# EM_Harp.net
KiCad netlist of a schematic drawn in EAGLE
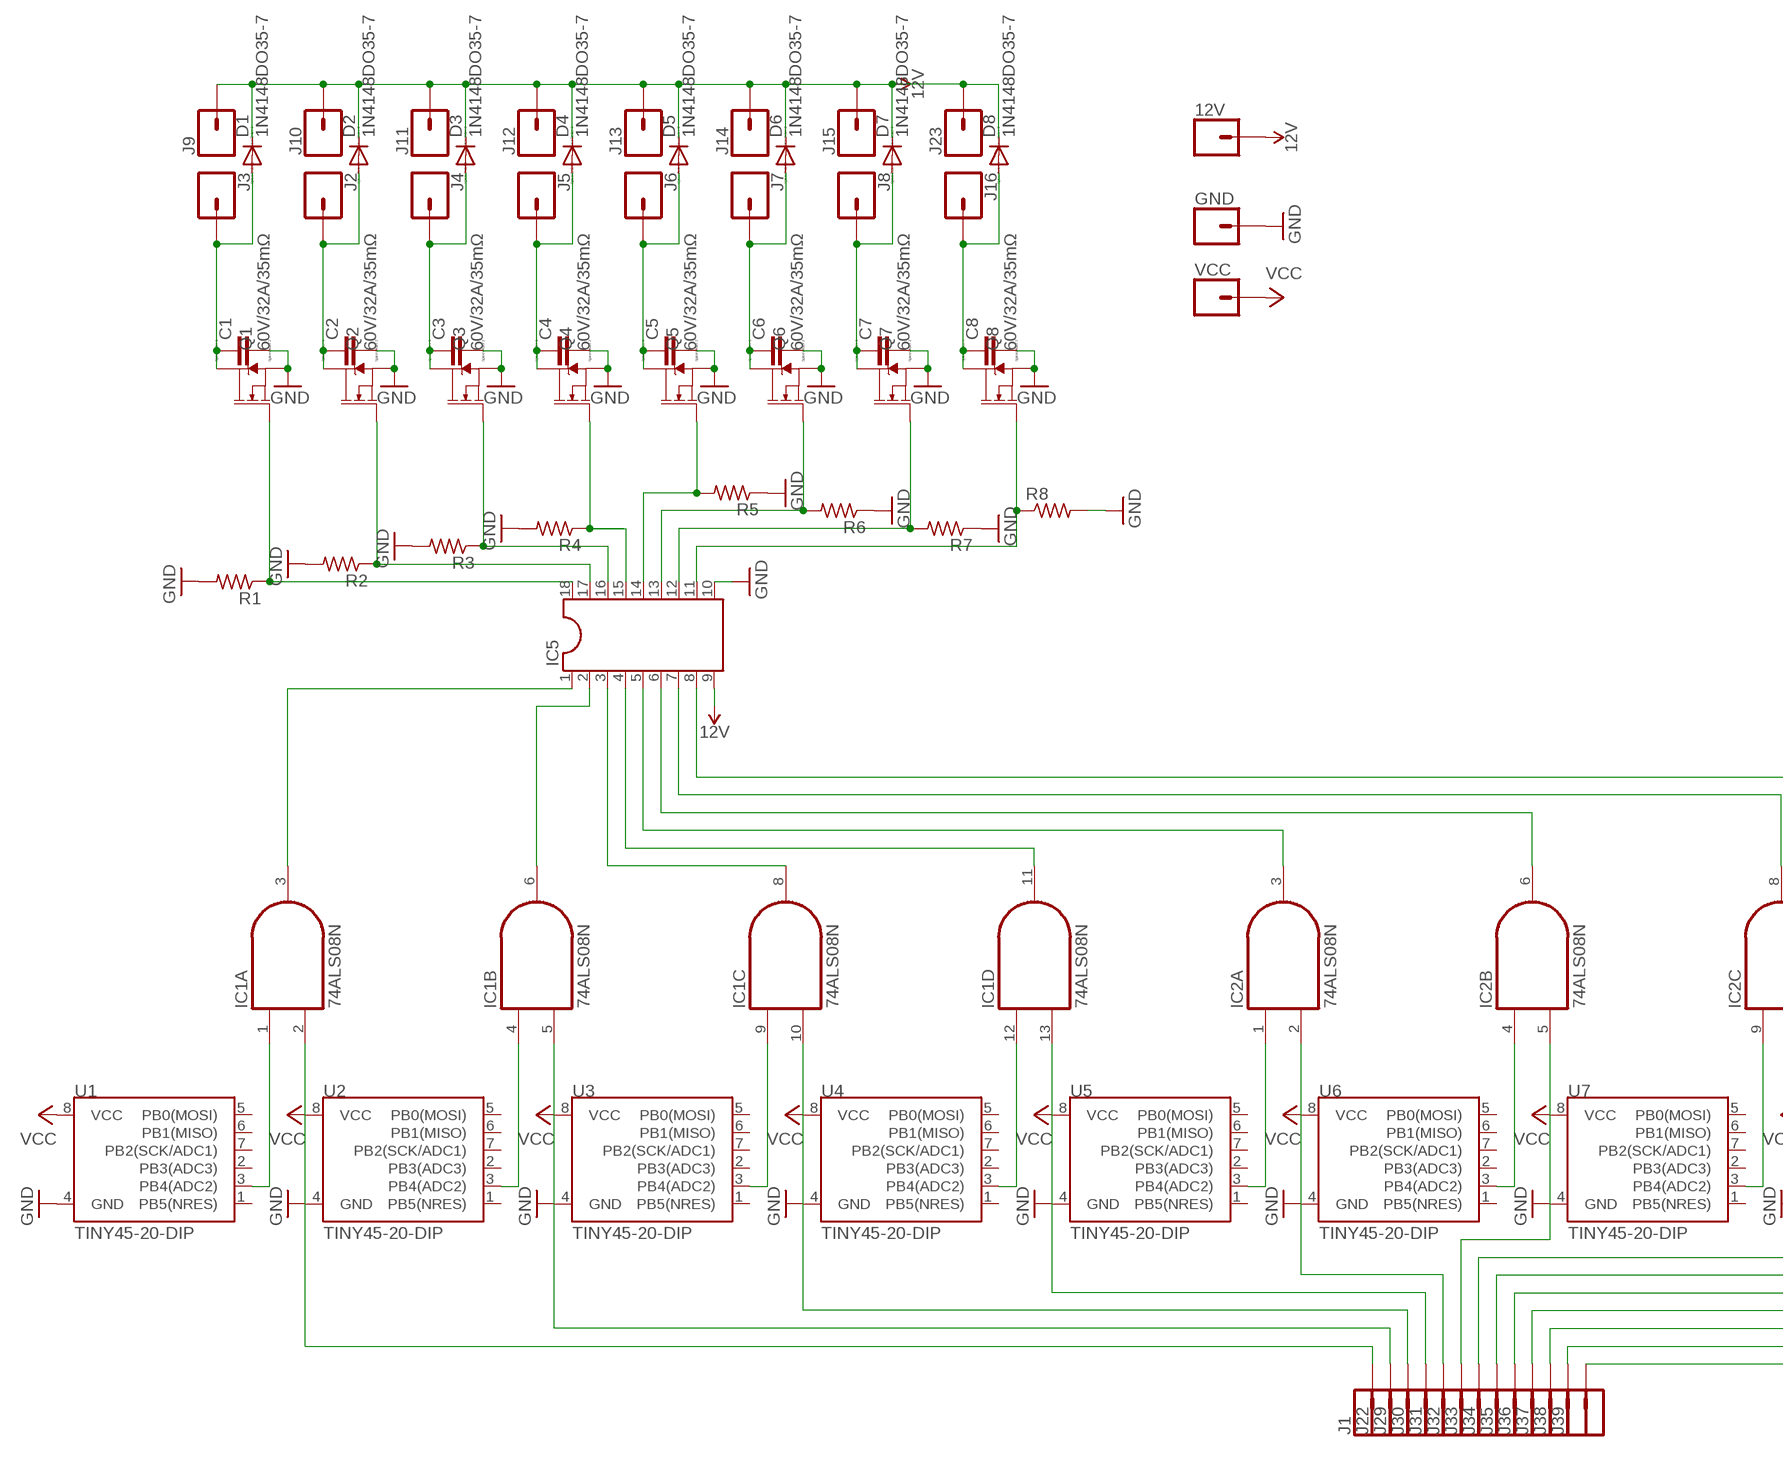
[diagram p0: schematic, sheet 1, part 1 of 2]
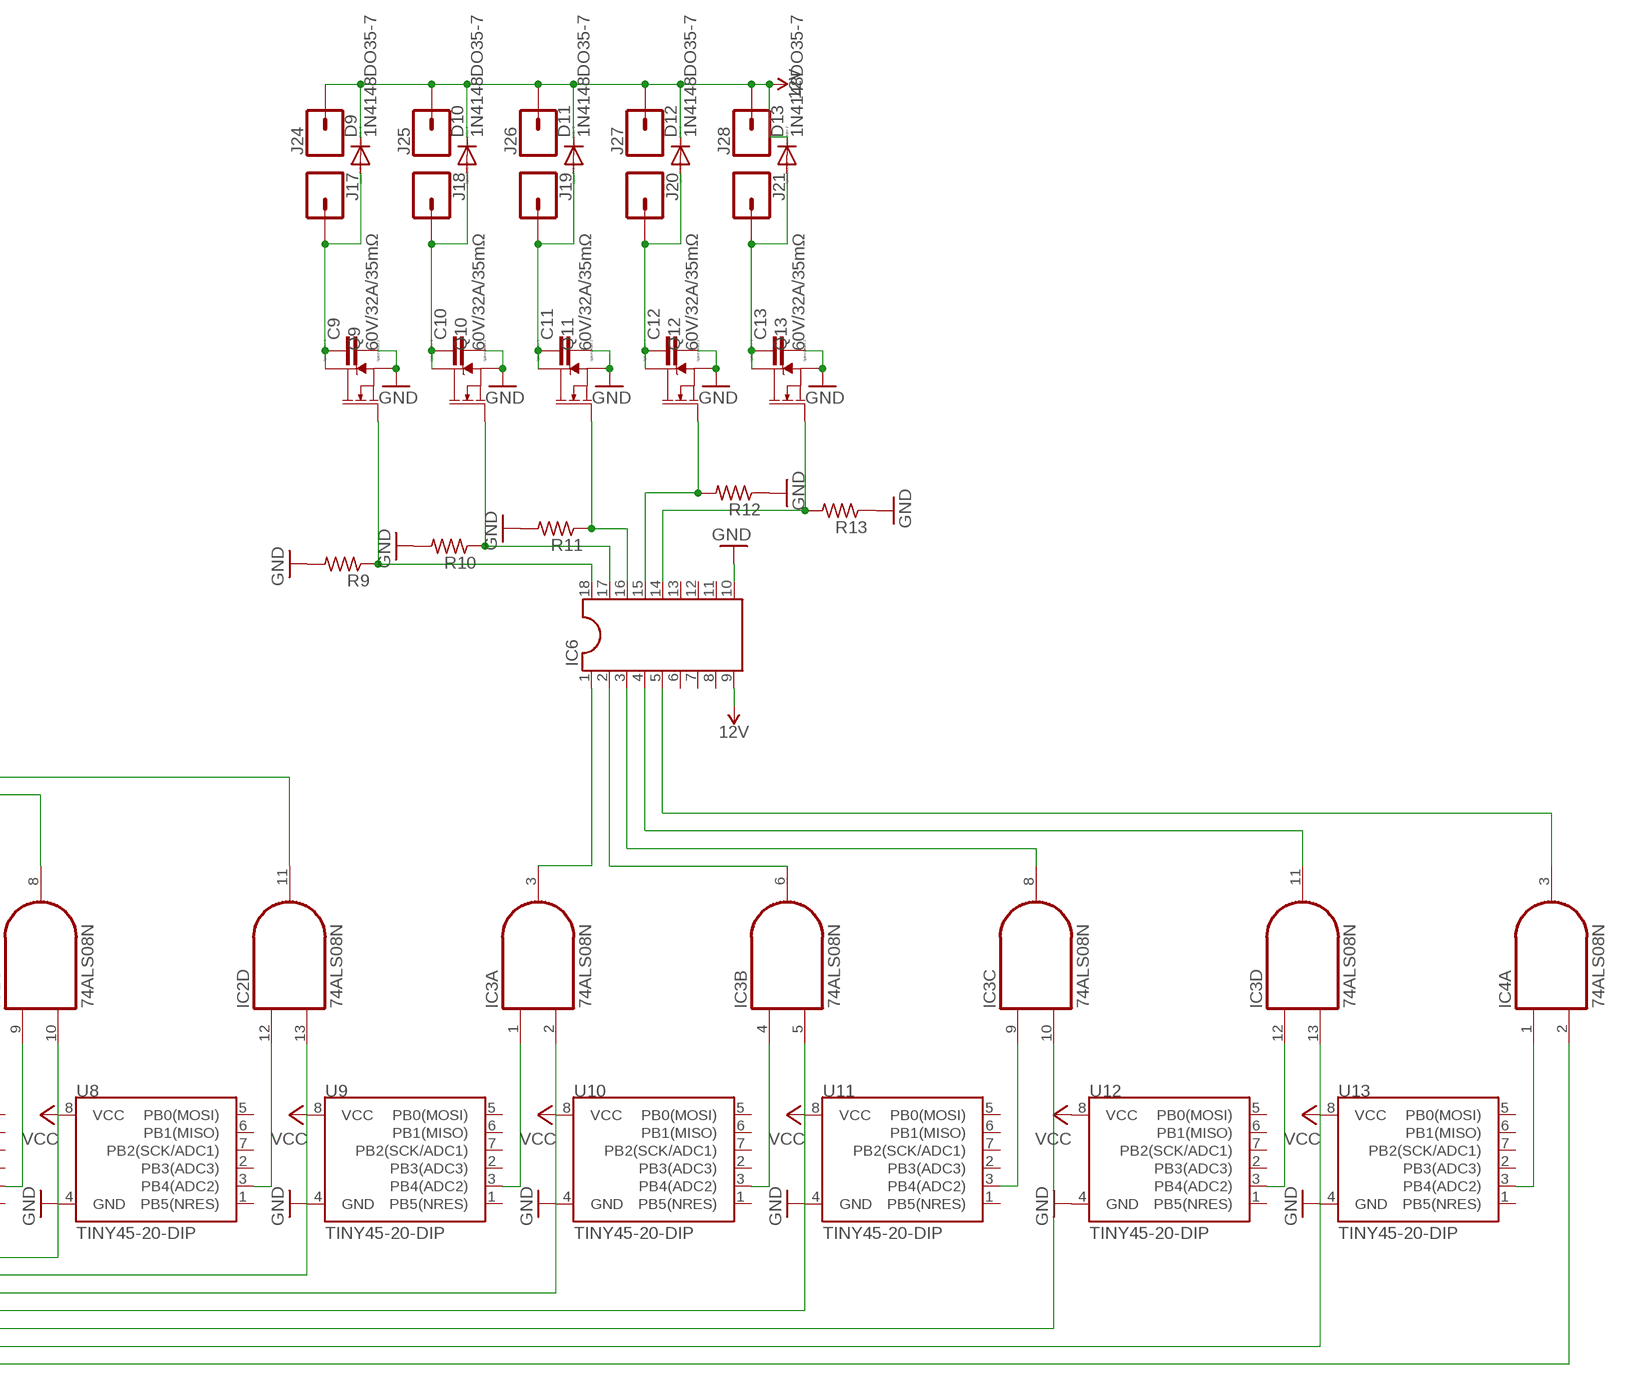
[diagram p1: schematic, sheet 1, part 2 of 2]

(export (version "E")
  (design (tool "Eeschema 10.0.6"))
  (components
    (comp (ref "12V")
      (value "CONN_01")
      (footprint "eagle-import:1X01")
      (libsource (lib "eagle-import") (part "CONN_01"))
    )
    (comp (ref "C1") (value "C") (footprint "eagle-import:C0805") (libsource (lib "eagle-import") (part "C")))
    (comp (ref "C2") (value "C") (footprint "eagle-import:C0805") (libsource (lib "eagle-import") (part "C")))
    (comp (ref "C3") (value "C") (footprint "eagle-import:C0805") (libsource (lib "eagle-import") (part "C")))
    (comp (ref "C4") (value "C") (footprint "eagle-import:C0805") (libsource (lib "eagle-import") (part "C")))
    (comp (ref "C5") (value "C") (footprint "eagle-import:C0805") (libsource (lib "eagle-import") (part "C")))
    (comp (ref "C6") (value "C") (footprint "eagle-import:C0805") (libsource (lib "eagle-import") (part "C")))
    (comp (ref "C7") (value "C") (footprint "eagle-import:C0805") (libsource (lib "eagle-import") (part "C")))
    (comp (ref "C8") (value "C") (footprint "eagle-import:C0805") (libsource (lib "eagle-import") (part "C")))
    (comp (ref "C9") (value "C") (footprint "eagle-import:C0805") (libsource (lib "eagle-import") (part "C")))
    (comp (ref "C10")
      (value "C")
      (footprint "eagle-import:C0805")
      (libsource (lib "eagle-import") (part "C"))
    )
    (comp (ref "C11")
      (value "C")
      (footprint "eagle-import:C0805")
      (libsource (lib "eagle-import") (part "C"))
    )
    (comp (ref "C12")
      (value "C")
      (footprint "eagle-import:C0805")
      (libsource (lib "eagle-import") (part "C"))
    )
    (comp (ref "C13")
      (value "C")
      (footprint "eagle-import:C0805")
      (libsource (lib "eagle-import") (part "C"))
    )
    (comp (ref "D1")
      (value "1N4148DO35-7")
      (footprint "eagle-import:DO35-7")
      (libsource (lib "eagle-import") (part "1N4148DO35-7"))
    )
    (comp (ref "D2")
      (value "1N4148DO35-7")
      (footprint "eagle-import:DO35-7")
      (libsource (lib "eagle-import") (part "1N4148DO35-7"))
    )
    (comp (ref "D3")
      (value "1N4148DO35-7")
      (footprint "eagle-import:DO35-7")
      (libsource (lib "eagle-import") (part "1N4148DO35-7"))
    )
    (comp (ref "D4")
      (value "1N4148DO35-7")
      (footprint "eagle-import:DO35-7")
      (libsource (lib "eagle-import") (part "1N4148DO35-7"))
    )
    (comp (ref "D5")
      (value "1N4148DO35-7")
      (footprint "eagle-import:DO35-7")
      (libsource (lib "eagle-import") (part "1N4148DO35-7"))
    )
    (comp (ref "D6")
      (value "1N4148DO35-7")
      (footprint "eagle-import:DO35-7")
      (libsource (lib "eagle-import") (part "1N4148DO35-7"))
    )
    (comp (ref "D7")
      (value "1N4148DO35-7")
      (footprint "eagle-import:DO35-7")
      (libsource (lib "eagle-import") (part "1N4148DO35-7"))
    )
    (comp (ref "D8")
      (value "1N4148DO35-7")
      (footprint "eagle-import:DO35-7")
      (libsource (lib "eagle-import") (part "1N4148DO35-7"))
    )
    (comp (ref "D9")
      (value "1N4148DO35-7")
      (footprint "eagle-import:DO35-7")
      (libsource (lib "eagle-import") (part "1N4148DO35-7"))
    )
    (comp (ref "D10")
      (value "1N4148DO35-7")
      (footprint "eagle-import:DO35-7")
      (libsource (lib "eagle-import") (part "1N4148DO35-7"))
    )
    (comp (ref "D11")
      (value "1N4148DO35-7")
      (footprint "eagle-import:DO35-7")
      (libsource (lib "eagle-import") (part "1N4148DO35-7"))
    )
    (comp (ref "D12")
      (value "1N4148DO35-7")
      (footprint "eagle-import:DO35-7")
      (libsource (lib "eagle-import") (part "1N4148DO35-7"))
    )
    (comp (ref "D13")
      (value "1N4148DO35-7")
      (footprint "eagle-import:DO35-7")
      (libsource (lib "eagle-import") (part "1N4148DO35-7"))
    )
    (comp (ref "GND")
      (value "CONN_01")
      (footprint "eagle-import:1X01")
      (libsource (lib "eagle-import") (part "CONN_01"))
    )
    (comp (ref "IC1")
      (value "74ALS08N")
      (footprint "eagle-import:DIL14")
      (libsource (lib "eagle-import") (part "7408NALS"))
    )
    (comp (ref "IC2")
      (value "74ALS08N")
      (footprint "eagle-import:DIL14")
      (libsource (lib "eagle-import") (part "7408NALS"))
    )
    (comp (ref "IC3")
      (value "74ALS08N")
      (footprint "eagle-import:DIL14")
      (libsource (lib "eagle-import") (part "7408NALS"))
    )
    (comp (ref "IC4")
      (value "74ALS08N")
      (footprint "eagle-import:DIL14")
      (libsource (lib "eagle-import") (part "7408NALS"))
    )
    (comp (ref "IC5")
      (value "DIL18")
      (footprint "eagle-import:DIL18")
      (libsource (lib "eagle-import") (part "DIL18"))
    )
    (comp (ref "IC6")
      (value "DIL18")
      (footprint "eagle-import:DIL18")
      (libsource (lib "eagle-import") (part "DIL18"))
    )
    (comp (ref "J1")
      (value "CONN_01")
      (footprint "eagle-import:1X01")
      (libsource (lib "eagle-import") (part "CONN_01"))
    )
    (comp (ref "J2")
      (value "CONN_01")
      (footprint "eagle-import:1X01")
      (libsource (lib "eagle-import") (part "CONN_01"))
    )
    (comp (ref "J3")
      (value "CONN_01")
      (footprint "eagle-import:1X01")
      (libsource (lib "eagle-import") (part "CONN_01"))
    )
    (comp (ref "J4")
      (value "CONN_01")
      (footprint "eagle-import:1X01")
      (libsource (lib "eagle-import") (part "CONN_01"))
    )
    (comp (ref "J5")
      (value "CONN_01")
      (footprint "eagle-import:1X01")
      (libsource (lib "eagle-import") (part "CONN_01"))
    )
    (comp (ref "J6")
      (value "CONN_01")
      (footprint "eagle-import:1X01")
      (libsource (lib "eagle-import") (part "CONN_01"))
    )
    (comp (ref "J7")
      (value "CONN_01")
      (footprint "eagle-import:1X01")
      (libsource (lib "eagle-import") (part "CONN_01"))
    )
    (comp (ref "J8")
      (value "CONN_01")
      (footprint "eagle-import:1X01")
      (libsource (lib "eagle-import") (part "CONN_01"))
    )
    (comp (ref "J9")
      (value "CONN_01")
      (footprint "eagle-import:1X01")
      (libsource (lib "eagle-import") (part "CONN_01"))
    )
    (comp (ref "J10")
      (value "CONN_01")
      (footprint "eagle-import:1X01")
      (libsource (lib "eagle-import") (part "CONN_01"))
    )
    (comp (ref "J11")
      (value "CONN_01")
      (footprint "eagle-import:1X01")
      (libsource (lib "eagle-import") (part "CONN_01"))
    )
    (comp (ref "J12")
      (value "CONN_01")
      (footprint "eagle-import:1X01")
      (libsource (lib "eagle-import") (part "CONN_01"))
    )
    (comp (ref "J13")
      (value "CONN_01")
      (footprint "eagle-import:1X01")
      (libsource (lib "eagle-import") (part "CONN_01"))
    )
    (comp (ref "J14")
      (value "CONN_01")
      (footprint "eagle-import:1X01")
      (libsource (lib "eagle-import") (part "CONN_01"))
    )
    (comp (ref "J15")
      (value "CONN_01")
      (footprint "eagle-import:1X01")
      (libsource (lib "eagle-import") (part "CONN_01"))
    )
    (comp (ref "J16")
      (value "CONN_01")
      (footprint "eagle-import:1X01")
      (libsource (lib "eagle-import") (part "CONN_01"))
    )
    (comp (ref "J17")
      (value "CONN_01")
      (footprint "eagle-import:1X01")
      (libsource (lib "eagle-import") (part "CONN_01"))
    )
    (comp (ref "J18")
      (value "CONN_01")
      (footprint "eagle-import:1X01")
      (libsource (lib "eagle-import") (part "CONN_01"))
    )
    (comp (ref "J19")
      (value "CONN_01")
      (footprint "eagle-import:1X01")
      (libsource (lib "eagle-import") (part "CONN_01"))
    )
    (comp (ref "J20")
      (value "CONN_01")
      (footprint "eagle-import:1X01")
      (libsource (lib "eagle-import") (part "CONN_01"))
    )
    (comp (ref "J21")
      (value "CONN_01")
      (footprint "eagle-import:1X01")
      (libsource (lib "eagle-import") (part "CONN_01"))
    )
    (comp (ref "J22")
      (value "CONN_01")
      (footprint "eagle-import:1X01")
      (libsource (lib "eagle-import") (part "CONN_01"))
    )
    (comp (ref "J23")
      (value "CONN_01")
      (footprint "eagle-import:1X01")
      (libsource (lib "eagle-import") (part "CONN_01"))
    )
    (comp (ref "J24")
      (value "CONN_01")
      (footprint "eagle-import:1X01")
      (libsource (lib "eagle-import") (part "CONN_01"))
    )
    (comp (ref "J25")
      (value "CONN_01")
      (footprint "eagle-import:1X01")
      (libsource (lib "eagle-import") (part "CONN_01"))
    )
    (comp (ref "J26")
      (value "CONN_01")
      (footprint "eagle-import:1X01")
      (libsource (lib "eagle-import") (part "CONN_01"))
    )
    (comp (ref "J27")
      (value "CONN_01")
      (footprint "eagle-import:1X01")
      (libsource (lib "eagle-import") (part "CONN_01"))
    )
    (comp (ref "J28")
      (value "CONN_01")
      (footprint "eagle-import:1X01")
      (libsource (lib "eagle-import") (part "CONN_01"))
    )
    (comp (ref "J29")
      (value "CONN_01")
      (footprint "eagle-import:1X01")
      (libsource (lib "eagle-import") (part "CONN_01"))
    )
    (comp (ref "J30")
      (value "CONN_01")
      (footprint "eagle-import:1X01")
      (libsource (lib "eagle-import") (part "CONN_01"))
    )
    (comp (ref "J31")
      (value "CONN_01")
      (footprint "eagle-import:1X01")
      (libsource (lib "eagle-import") (part "CONN_01"))
    )
    (comp (ref "J32")
      (value "CONN_01")
      (footprint "eagle-import:1X01")
      (libsource (lib "eagle-import") (part "CONN_01"))
    )
    (comp (ref "J33")
      (value "CONN_01")
      (footprint "eagle-import:1X01")
      (libsource (lib "eagle-import") (part "CONN_01"))
    )
    (comp (ref "J34")
      (value "CONN_01")
      (footprint "eagle-import:1X01")
      (libsource (lib "eagle-import") (part "CONN_01"))
    )
    (comp (ref "J35")
      (value "CONN_01")
      (footprint "eagle-import:1X01")
      (libsource (lib "eagle-import") (part "CONN_01"))
    )
    (comp (ref "J36")
      (value "CONN_01")
      (footprint "eagle-import:1X01")
      (libsource (lib "eagle-import") (part "CONN_01"))
    )
    (comp (ref "J37")
      (value "CONN_01")
      (footprint "eagle-import:1X01")
      (libsource (lib "eagle-import") (part "CONN_01"))
    )
    (comp (ref "J38")
      (value "CONN_01")
      (footprint "eagle-import:1X01")
      (libsource (lib "eagle-import") (part "CONN_01"))
    )
    (comp (ref "J39")
      (value "CONN_01")
      (footprint "eagle-import:1X01")
      (libsource (lib "eagle-import") (part "CONN_01"))
    )
    (comp (ref "Q1")
      (value "60V/32A/35mΩ")
      (footprint "eagle-import:TO220V")
      (libsource (lib "eagle-import") (part "MOSFET-NCH-FQP30N06L"))
    )
    (comp (ref "Q2")
      (value "60V/32A/35mΩ")
      (footprint "eagle-import:TO220V")
      (libsource (lib "eagle-import") (part "MOSFET-NCH-FQP30N06L"))
    )
    (comp (ref "Q3")
      (value "60V/32A/35mΩ")
      (footprint "eagle-import:TO220V")
      (libsource (lib "eagle-import") (part "MOSFET-NCH-FQP30N06L"))
    )
    (comp (ref "Q4")
      (value "60V/32A/35mΩ")
      (footprint "eagle-import:TO220V")
      (libsource (lib "eagle-import") (part "MOSFET-NCH-FQP30N06L"))
    )
    (comp (ref "Q5")
      (value "60V/32A/35mΩ")
      (footprint "eagle-import:TO220V")
      (libsource (lib "eagle-import") (part "MOSFET-NCH-FQP30N06L"))
    )
    (comp (ref "Q6")
      (value "60V/32A/35mΩ")
      (footprint "eagle-import:TO220V")
      (libsource (lib "eagle-import") (part "MOSFET-NCH-FQP30N06L"))
    )
    (comp (ref "Q7")
      (value "60V/32A/35mΩ")
      (footprint "eagle-import:TO220V")
      (libsource (lib "eagle-import") (part "MOSFET-NCH-FQP30N06L"))
    )
    (comp (ref "Q8")
      (value "60V/32A/35mΩ")
      (footprint "eagle-import:TO220V")
      (libsource (lib "eagle-import") (part "MOSFET-NCH-FQP30N06L"))
    )
    (comp (ref "Q9")
      (value "60V/32A/35mΩ")
      (footprint "eagle-import:TO220V")
      (libsource (lib "eagle-import") (part "MOSFET-NCH-FQP30N06L"))
    )
    (comp (ref "Q10")
      (value "60V/32A/35mΩ")
      (footprint "eagle-import:TO220V")
      (libsource (lib "eagle-import") (part "MOSFET-NCH-FQP30N06L"))
    )
    (comp (ref "Q11")
      (value "60V/32A/35mΩ")
      (footprint "eagle-import:TO220V")
      (libsource (lib "eagle-import") (part "MOSFET-NCH-FQP30N06L"))
    )
    (comp (ref "Q12")
      (value "60V/32A/35mΩ")
      (footprint "eagle-import:TO220V")
      (libsource (lib "eagle-import") (part "MOSFET-NCH-FQP30N06L"))
    )
    (comp (ref "Q13")
      (value "60V/32A/35mΩ")
      (footprint "eagle-import:TO220V")
      (libsource (lib "eagle-import") (part "MOSFET-NCH-FQP30N06L"))
    )
    (comp (ref "R1")
      (value "R-US_M0805")
      (footprint "eagle-import:M0805")
      (libsource (lib "eagle-import") (part "R-US_M0805"))
    )
    (comp (ref "R2")
      (value "R-US_R0805")
      (footprint "eagle-import:R0805")
      (libsource (lib "eagle-import") (part "R-US_R0805"))
    )
    (comp (ref "R3")
      (value "R-US_R0805")
      (footprint "eagle-import:R0805")
      (libsource (lib "eagle-import") (part "R-US_R0805"))
    )
    (comp (ref "R4")
      (value "R-US_R0805")
      (footprint "eagle-import:R0805")
      (libsource (lib "eagle-import") (part "R-US_R0805"))
    )
    (comp (ref "R5")
      (value "R-US_R0805")
      (footprint "eagle-import:R0805")
      (libsource (lib "eagle-import") (part "R-US_R0805"))
    )
    (comp (ref "R6")
      (value "R-US_R0805")
      (footprint "eagle-import:R0805")
      (libsource (lib "eagle-import") (part "R-US_R0805"))
    )
    (comp (ref "R7")
      (value "R-US_R0805")
      (footprint "eagle-import:R0805")
      (libsource (lib "eagle-import") (part "R-US_R0805"))
    )
    (comp (ref "R8")
      (value "R-US_R0805")
      (footprint "eagle-import:R0805")
      (libsource (lib "eagle-import") (part "R-US_R0805"))
    )
    (comp (ref "R9")
      (value "R-US_R0805")
      (footprint "eagle-import:R0805")
      (libsource (lib "eagle-import") (part "R-US_R0805"))
    )
    (comp (ref "R10")
      (value "R-US_R0805")
      (footprint "eagle-import:R0805")
      (libsource (lib "eagle-import") (part "R-US_R0805"))
    )
    (comp (ref "R11")
      (value "R-US_R0805")
      (footprint "eagle-import:R0805")
      (libsource (lib "eagle-import") (part "R-US_R0805"))
    )
    (comp (ref "R12")
      (value "R-US_R0805")
      (footprint "eagle-import:R0805")
      (libsource (lib "eagle-import") (part "R-US_R0805"))
    )
    (comp (ref "R13")
      (value "R-US_R0805")
      (footprint "eagle-import:R0805")
      (libsource (lib "eagle-import") (part "R-US_R0805"))
    )
    (comp (ref "U1")
      (value "TINY45-20-DIP")
      (footprint "eagle-import:DIP08_MCU")
      (libsource (lib "eagle-import") (part "ATTINY45TINY45-20-DIP"))
    )
    (comp (ref "U2")
      (value "TINY45-20-DIP")
      (footprint "eagle-import:DIP08_MCU")
      (libsource (lib "eagle-import") (part "ATTINY45TINY45-20-DIP"))
    )
    (comp (ref "U3")
      (value "TINY45-20-DIP")
      (footprint "eagle-import:DIP08_MCU")
      (libsource (lib "eagle-import") (part "ATTINY45TINY45-20-DIP"))
    )
    (comp (ref "U4")
      (value "TINY45-20-DIP")
      (footprint "eagle-import:DIP08_MCU")
      (libsource (lib "eagle-import") (part "ATTINY45TINY45-20-DIP"))
    )
    (comp (ref "U5")
      (value "TINY45-20-DIP")
      (footprint "eagle-import:DIP08_MCU")
      (libsource (lib "eagle-import") (part "ATTINY45TINY45-20-DIP"))
    )
    (comp (ref "U6")
      (value "TINY45-20-DIP")
      (footprint "eagle-import:DIP08_MCU")
      (libsource (lib "eagle-import") (part "ATTINY45TINY45-20-DIP"))
    )
    (comp (ref "U7")
      (value "TINY45-20-DIP")
      (footprint "eagle-import:DIP08_MCU")
      (libsource (lib "eagle-import") (part "ATTINY45TINY45-20-DIP"))
    )
    (comp (ref "U8")
      (value "TINY45-20-DIP")
      (footprint "eagle-import:DIP08_MCU")
      (libsource (lib "eagle-import") (part "ATTINY45TINY45-20-DIP"))
    )
    (comp (ref "U9")
      (value "TINY45-20-DIP")
      (footprint "eagle-import:DIP08_MCU")
      (libsource (lib "eagle-import") (part "ATTINY45TINY45-20-DIP"))
    )
    (comp (ref "U10")
      (value "TINY45-20-DIP")
      (footprint "eagle-import:DIP08_MCU")
      (libsource (lib "eagle-import") (part "ATTINY45TINY45-20-DIP"))
    )
    (comp (ref "U11")
      (value "TINY45-20-DIP")
      (footprint "eagle-import:DIP08_MCU")
      (libsource (lib "eagle-import") (part "ATTINY45TINY45-20-DIP"))
    )
    (comp (ref "U12")
      (value "TINY45-20-DIP")
      (footprint "eagle-import:DIP08_MCU")
      (libsource (lib "eagle-import") (part "ATTINY45TINY45-20-DIP"))
    )
    (comp (ref "U13")
      (value "TINY45-20-DIP")
      (footprint "eagle-import:DIP08_MCU")
      (libsource (lib "eagle-import") (part "ATTINY45TINY45-20-DIP"))
    )
    (comp (ref "VCC")
      (value "CONN_01")
      (footprint "eagle-import:1X01")
      (libsource (lib "eagle-import") (part "CONN_01"))
    )
  )
  (nets
    (net (code "1") (name "12V") (class "Default")
      (node (ref "12V") (pin "1") (pinfunction "1_1") (pintype "passive"))
      (node (ref "D1") (pin "C") (pinfunction "C_C") (pintype "passive"))
      (node (ref "D10") (pin "C") (pinfunction "C_C") (pintype "passive"))
      (node (ref "D11") (pin "C") (pinfunction "C_C") (pintype "passive"))
      (node (ref "D12") (pin "C") (pinfunction "C_C") (pintype "passive"))
      (node (ref "D13") (pin "C") (pinfunction "C_C") (pintype "passive"))
      (node (ref "D2") (pin "C") (pinfunction "C_C") (pintype "passive"))
      (node (ref "D3") (pin "C") (pinfunction "C_C") (pintype "passive"))
      (node (ref "D4") (pin "C") (pinfunction "C_C") (pintype "passive"))
      (node (ref "D5") (pin "C") (pinfunction "C_C") (pintype "passive"))
      (node (ref "D6") (pin "C") (pinfunction "C_C") (pintype "passive"))
      (node (ref "D7") (pin "C") (pinfunction "C_C") (pintype "passive"))
      (node (ref "D8") (pin "C") (pinfunction "C_C") (pintype "passive"))
      (node (ref "D9") (pin "C") (pinfunction "C_C") (pintype "passive"))
      (node (ref "IC5") (pin "9") (pinfunction "9_9") (pintype "passive"))
      (node (ref "IC6") (pin "9") (pinfunction "9_9") (pintype "passive"))
      (node (ref "J10") (pin "1") (pinfunction "1_1") (pintype "passive"))
      (node (ref "J11") (pin "1") (pinfunction "1_1") (pintype "passive"))
      (node (ref "J12") (pin "1") (pinfunction "1_1") (pintype "passive"))
      (node (ref "J13") (pin "1") (pinfunction "1_1") (pintype "passive"))
      (node (ref "J14") (pin "1") (pinfunction "1_1") (pintype "passive"))
      (node (ref "J15") (pin "1") (pinfunction "1_1") (pintype "passive"))
      (node (ref "J23") (pin "1") (pinfunction "1_1") (pintype "passive"))
      (node (ref "J24") (pin "1") (pinfunction "1_1") (pintype "passive"))
      (node (ref "J25") (pin "1") (pinfunction "1_1") (pintype "passive"))
      (node (ref "J26") (pin "1") (pinfunction "1_1") (pintype "passive"))
      (node (ref "J27") (pin "1") (pinfunction "1_1") (pintype "passive"))
      (node (ref "J28") (pin "1") (pinfunction "1_1") (pintype "passive"))
      (node (ref "J9") (pin "1") (pinfunction "1_1") (pintype "passive"))
    )
    (net (code "2") (name "GND") (class "Default")
      (node (ref "C1") (pin "2") (pinfunction "2_2") (pintype "passive"))
      (node (ref "C10") (pin "2") (pinfunction "2_2") (pintype "passive"))
      (node (ref "C11") (pin "2") (pinfunction "2_2") (pintype "passive"))
      (node (ref "C12") (pin "2") (pinfunction "2_2") (pintype "passive"))
      (node (ref "C13") (pin "2") (pinfunction "2_2") (pintype "passive"))
      (node (ref "C2") (pin "2") (pinfunction "2_2") (pintype "passive"))
      (node (ref "C3") (pin "2") (pinfunction "2_2") (pintype "passive"))
      (node (ref "C4") (pin "2") (pinfunction "2_2") (pintype "passive"))
      (node (ref "C5") (pin "2") (pinfunction "2_2") (pintype "passive"))
      (node (ref "C6") (pin "2") (pinfunction "2_2") (pintype "passive"))
      (node (ref "C7") (pin "2") (pinfunction "2_2") (pintype "passive"))
      (node (ref "C8") (pin "2") (pinfunction "2_2") (pintype "passive"))
      (node (ref "C9") (pin "2") (pinfunction "2_2") (pintype "passive"))
      (node (ref "GND") (pin "1") (pinfunction "1_1") (pintype "passive"))
      (node (ref "IC5") (pin "10") (pinfunction "10_10") (pintype "passive"))
      (node (ref "IC6") (pin "10") (pinfunction "10_10") (pintype "passive"))
      (node (ref "Q1") (pin "3") (pinfunction "S_3") (pintype "bidirectional"))
      (node (ref "Q10") (pin "3") (pinfunction "S_3") (pintype "bidirectional"))
      (node (ref "Q11") (pin "3") (pinfunction "S_3") (pintype "bidirectional"))
      (node (ref "Q12") (pin "3") (pinfunction "S_3") (pintype "bidirectional"))
      (node (ref "Q13") (pin "3") (pinfunction "S_3") (pintype "bidirectional"))
      (node (ref "Q2") (pin "3") (pinfunction "S_3") (pintype "bidirectional"))
      (node (ref "Q3") (pin "3") (pinfunction "S_3") (pintype "bidirectional"))
      (node (ref "Q4") (pin "3") (pinfunction "S_3") (pintype "bidirectional"))
      (node (ref "Q5") (pin "3") (pinfunction "S_3") (pintype "bidirectional"))
      (node (ref "Q6") (pin "3") (pinfunction "S_3") (pintype "bidirectional"))
      (node (ref "Q7") (pin "3") (pinfunction "S_3") (pintype "bidirectional"))
      (node (ref "Q8") (pin "3") (pinfunction "S_3") (pintype "bidirectional"))
      (node (ref "Q9") (pin "3") (pinfunction "S_3") (pintype "bidirectional"))
      (node (ref "R1") (pin "2") (pinfunction "2_2") (pintype "passive"))
      (node (ref "R10") (pin "2") (pinfunction "2_2") (pintype "passive"))
      (node (ref "R11") (pin "2") (pinfunction "2_2") (pintype "passive"))
      (node (ref "R12") (pin "1") (pinfunction "1_1") (pintype "passive"))
      (node (ref "R13") (pin "1") (pinfunction "1_1") (pintype "passive"))
      (node (ref "R2") (pin "2") (pinfunction "2_2") (pintype "passive"))
      (node (ref "R3") (pin "2") (pinfunction "2_2") (pintype "passive"))
      (node (ref "R4") (pin "2") (pinfunction "2_2") (pintype "passive"))
      (node (ref "R5") (pin "1") (pinfunction "1_1") (pintype "passive"))
      (node (ref "R6") (pin "1") (pinfunction "1_1") (pintype "passive"))
      (node (ref "R7") (pin "1") (pinfunction "1_1") (pintype "passive"))
      (node (ref "R8") (pin "2") (pinfunction "2_2") (pintype "passive"))
      (node (ref "R9") (pin "2") (pinfunction "2_2") (pintype "passive"))
      (node (ref "U1") (pin "4") (pinfunction "GND_4") (pintype "bidirectional"))
      (node (ref "U10") (pin "4") (pinfunction "GND_4") (pintype "bidirectional"))
      (node (ref "U11") (pin "4") (pinfunction "GND_4") (pintype "bidirectional"))
      (node (ref "U12") (pin "4") (pinfunction "GND_4") (pintype "bidirectional"))
      (node (ref "U13") (pin "4") (pinfunction "GND_4") (pintype "bidirectional"))
      (node (ref "U2") (pin "4") (pinfunction "GND_4") (pintype "bidirectional"))
      (node (ref "U3") (pin "4") (pinfunction "GND_4") (pintype "bidirectional"))
      (node (ref "U4") (pin "4") (pinfunction "GND_4") (pintype "bidirectional"))
      (node (ref "U5") (pin "4") (pinfunction "GND_4") (pintype "bidirectional"))
      (node (ref "U6") (pin "4") (pinfunction "GND_4") (pintype "bidirectional"))
      (node (ref "U7") (pin "4") (pinfunction "GND_4") (pintype "bidirectional"))
      (node (ref "U8") (pin "4") (pinfunction "GND_4") (pintype "bidirectional"))
      (node (ref "U9") (pin "4") (pinfunction "GND_4") (pintype "bidirectional"))
    )
    (net (code "3") (name "Net-(IC1A-I0)") (class "Default")
      (node (ref "IC1") (pin "1") (pinfunction "I0_1") (pintype "input"))
      (node (ref "U1") (pin "3") (pinfunction "PB4(ADC2)_3") (pintype "bidirectional"))
    )
    (net (code "4") (name "Net-(IC1A-I1)") (class "Default")
      (node (ref "IC1") (pin "2") (pinfunction "I1_2") (pintype "input"))
      (node (ref "J1") (pin "1") (pinfunction "1_1") (pintype "passive"))
    )
    (net (code "5") (name "Net-(IC1A-O)") (class "Default")
      (node (ref "IC1") (pin "3") (pinfunction "O_3") (pintype "output"))
      (node (ref "IC5") (pin "1") (pinfunction "1_1") (pintype "passive"))
    )
    (net (code "6") (name "Net-(IC1B-I0)") (class "Default")
      (node (ref "IC1") (pin "4") (pinfunction "I0_4") (pintype "input"))
      (node (ref "U2") (pin "3") (pinfunction "PB4(ADC2)_3") (pintype "bidirectional"))
    )
    (net (code "7") (name "Net-(IC1B-I1)") (class "Default")
      (node (ref "IC1") (pin "5") (pinfunction "I1_5") (pintype "input"))
      (node (ref "J22") (pin "1") (pinfunction "1_1") (pintype "passive"))
    )
    (net (code "8") (name "Net-(IC1B-O)") (class "Default")
      (node (ref "IC1") (pin "6") (pinfunction "O_6") (pintype "output"))
      (node (ref "IC5") (pin "2") (pinfunction "2_2") (pintype "passive"))
    )
    (net (code "9") (name "Net-(IC1C-I0)") (class "Default")
      (node (ref "IC1") (pin "9") (pinfunction "I0_9") (pintype "input"))
      (node (ref "U3") (pin "3") (pinfunction "PB4(ADC2)_3") (pintype "bidirectional"))
    )
    (net (code "10") (name "Net-(IC1C-I1)") (class "Default")
      (node (ref "IC1") (pin "10") (pinfunction "I1_10") (pintype "input"))
      (node (ref "J29") (pin "1") (pinfunction "1_1") (pintype "passive"))
    )
    (net (code "11") (name "Net-(IC1C-O)") (class "Default")
      (node (ref "IC1") (pin "8") (pinfunction "O_8") (pintype "output"))
      (node (ref "IC5") (pin "3") (pinfunction "3_3") (pintype "passive"))
    )
    (net (code "12") (name "Net-(IC1D-I0)") (class "Default")
      (node (ref "IC1") (pin "12") (pinfunction "I0_12") (pintype "input"))
      (node (ref "U4") (pin "3") (pinfunction "PB4(ADC2)_3") (pintype "bidirectional"))
    )
    (net (code "13") (name "Net-(IC1D-I1)") (class "Default")
      (node (ref "IC1") (pin "13") (pinfunction "I1_13") (pintype "input"))
      (node (ref "J30") (pin "1") (pinfunction "1_1") (pintype "passive"))
    )
    (net (code "14") (name "Net-(IC1D-O)") (class "Default")
      (node (ref "IC1") (pin "11") (pinfunction "O_11") (pintype "output"))
      (node (ref "IC5") (pin "4") (pinfunction "4_4") (pintype "passive"))
    )
    (net (code "15") (name "Net-(IC2A-I0)") (class "Default")
      (node (ref "IC2") (pin "1") (pinfunction "I0_1") (pintype "input"))
      (node (ref "U5") (pin "3") (pinfunction "PB4(ADC2)_3") (pintype "bidirectional"))
    )
    (net (code "16") (name "Net-(IC2A-I1)") (class "Default")
      (node (ref "IC2") (pin "2") (pinfunction "I1_2") (pintype "input"))
      (node (ref "J31") (pin "1") (pinfunction "1_1") (pintype "passive"))
    )
    (net (code "17") (name "Net-(IC2A-O)") (class "Default")
      (node (ref "IC2") (pin "3") (pinfunction "O_3") (pintype "output"))
      (node (ref "IC5") (pin "5") (pinfunction "5_5") (pintype "passive"))
    )
    (net (code "18") (name "Net-(IC2B-I0)") (class "Default")
      (node (ref "IC2") (pin "4") (pinfunction "I0_4") (pintype "input"))
      (node (ref "U6") (pin "3") (pinfunction "PB4(ADC2)_3") (pintype "bidirectional"))
    )
    (net (code "19") (name "Net-(IC2B-I1)") (class "Default")
      (node (ref "IC2") (pin "5") (pinfunction "I1_5") (pintype "input"))
      (node (ref "J32") (pin "1") (pinfunction "1_1") (pintype "passive"))
    )
    (net (code "20") (name "Net-(IC2B-O)") (class "Default")
      (node (ref "IC2") (pin "6") (pinfunction "O_6") (pintype "output"))
      (node (ref "IC5") (pin "6") (pinfunction "6_6") (pintype "passive"))
    )
    (net (code "21") (name "Net-(IC2C-I0)") (class "Default")
      (node (ref "IC2") (pin "9") (pinfunction "I0_9") (pintype "input"))
      (node (ref "U7") (pin "3") (pinfunction "PB4(ADC2)_3") (pintype "bidirectional"))
    )
    (net (code "22") (name "Net-(IC2C-I1)") (class "Default")
      (node (ref "IC2") (pin "10") (pinfunction "I1_10") (pintype "input"))
      (node (ref "J33") (pin "1") (pinfunction "1_1") (pintype "passive"))
    )
    (net (code "23") (name "Net-(IC2C-O)") (class "Default")
      (node (ref "IC2") (pin "8") (pinfunction "O_8") (pintype "output"))
      (node (ref "IC5") (pin "7") (pinfunction "7_7") (pintype "passive"))
    )
    (net (code "24") (name "Net-(IC2D-I0)") (class "Default")
      (node (ref "IC2") (pin "12") (pinfunction "I0_12") (pintype "input"))
      (node (ref "U8") (pin "3") (pinfunction "PB4(ADC2)_3") (pintype "bidirectional"))
    )
    (net (code "25") (name "Net-(IC2D-I1)") (class "Default")
      (node (ref "IC2") (pin "13") (pinfunction "I1_13") (pintype "input"))
      (node (ref "J34") (pin "1") (pinfunction "1_1") (pintype "passive"))
    )
    (net (code "26") (name "Net-(IC2D-O)") (class "Default")
      (node (ref "IC2") (pin "11") (pinfunction "O_11") (pintype "output"))
      (node (ref "IC5") (pin "8") (pinfunction "8_8") (pintype "passive"))
    )
    (net (code "27") (name "Net-(IC3A-I0)") (class "Default")
      (node (ref "IC3") (pin "1") (pinfunction "I0_1") (pintype "input"))
      (node (ref "U9") (pin "3") (pinfunction "PB4(ADC2)_3") (pintype "bidirectional"))
    )
    (net (code "28") (name "Net-(IC3A-I1)") (class "Default")
      (node (ref "IC3") (pin "2") (pinfunction "I1_2") (pintype "input"))
      (node (ref "J35") (pin "1") (pinfunction "1_1") (pintype "passive"))
    )
    (net (code "29") (name "Net-(IC3A-O)") (class "Default")
      (node (ref "IC3") (pin "3") (pinfunction "O_3") (pintype "output"))
      (node (ref "IC6") (pin "1") (pinfunction "1_1") (pintype "passive"))
    )
    (net (code "30") (name "Net-(IC3B-I0)") (class "Default")
      (node (ref "IC3") (pin "4") (pinfunction "I0_4") (pintype "input"))
      (node (ref "U10") (pin "3") (pinfunction "PB4(ADC2)_3") (pintype "bidirectional"))
    )
    (net (code "31") (name "Net-(IC3B-I1)") (class "Default")
      (node (ref "IC3") (pin "5") (pinfunction "I1_5") (pintype "input"))
      (node (ref "J36") (pin "1") (pinfunction "1_1") (pintype "passive"))
    )
    (net (code "32") (name "Net-(IC3B-O)") (class "Default")
      (node (ref "IC3") (pin "6") (pinfunction "O_6") (pintype "output"))
      (node (ref "IC6") (pin "2") (pinfunction "2_2") (pintype "passive"))
    )
    (net (code "33") (name "Net-(IC3C-I0)") (class "Default")
      (node (ref "IC3") (pin "9") (pinfunction "I0_9") (pintype "input"))
      (node (ref "U11") (pin "3") (pinfunction "PB4(ADC2)_3") (pintype "bidirectional"))
    )
    (net (code "34") (name "Net-(IC3C-I1)") (class "Default")
      (node (ref "IC3") (pin "10") (pinfunction "I1_10") (pintype "input"))
      (node (ref "J37") (pin "1") (pinfunction "1_1") (pintype "passive"))
    )
    (net (code "35") (name "Net-(IC3C-O)") (class "Default")
      (node (ref "IC3") (pin "8") (pinfunction "O_8") (pintype "output"))
      (node (ref "IC6") (pin "3") (pinfunction "3_3") (pintype "passive"))
    )
    (net (code "36") (name "Net-(IC3D-I0)") (class "Default")
      (node (ref "IC3") (pin "12") (pinfunction "I0_12") (pintype "input"))
      (node (ref "U12") (pin "3") (pinfunction "PB4(ADC2)_3") (pintype "bidirectional"))
    )
    (net (code "37") (name "Net-(IC3D-I1)") (class "Default")
      (node (ref "IC3") (pin "13") (pinfunction "I1_13") (pintype "input"))
      (node (ref "J38") (pin "1") (pinfunction "1_1") (pintype "passive"))
    )
    (net (code "38") (name "Net-(IC3D-O)") (class "Default")
      (node (ref "IC3") (pin "11") (pinfunction "O_11") (pintype "output"))
      (node (ref "IC6") (pin "4") (pinfunction "4_4") (pintype "passive"))
    )
    (net (code "39") (name "Net-(IC4A-I0)") (class "Default")
      (node (ref "IC4") (pin "1") (pinfunction "I0_1") (pintype "input"))
      (node (ref "U13") (pin "3") (pinfunction "PB4(ADC2)_3") (pintype "bidirectional"))
    )
    (net (code "40") (name "Net-(IC4A-I1)") (class "Default")
      (node (ref "IC4") (pin "2") (pinfunction "I1_2") (pintype "input"))
      (node (ref "J39") (pin "1") (pinfunction "1_1") (pintype "passive"))
    )
    (net (code "41") (name "Net-(IC4A-O)") (class "Default")
      (node (ref "IC4") (pin "3") (pinfunction "O_3") (pintype "output"))
      (node (ref "IC6") (pin "5") (pinfunction "5_5") (pintype "passive"))
    )
    (net (code "42") (name "Net-(Q1-D)") (class "Default")
      (node (ref "C1") (pin "1") (pinfunction "1_1") (pintype "passive"))
      (node (ref "D1") (pin "A") (pinfunction "A_A") (pintype "passive"))
      (node (ref "J3") (pin "1") (pinfunction "1_1") (pintype "passive"))
      (node (ref "Q1") (pin "2") (pinfunction "D_2") (pintype "bidirectional"))
    )
    (net (code "43") (name "Net-(Q1-G)") (class "Default")
      (node (ref "IC5") (pin "18") (pinfunction "18_18") (pintype "passive"))
      (node (ref "Q1") (pin "1") (pinfunction "G_1") (pintype "bidirectional"))
      (node (ref "R1") (pin "1") (pinfunction "1_1") (pintype "passive"))
    )
    (net (code "44") (name "Net-(Q2-D)") (class "Default")
      (node (ref "C2") (pin "1") (pinfunction "1_1") (pintype "passive"))
      (node (ref "D2") (pin "A") (pinfunction "A_A") (pintype "passive"))
      (node (ref "J2") (pin "1") (pinfunction "1_1") (pintype "passive"))
      (node (ref "Q2") (pin "2") (pinfunction "D_2") (pintype "bidirectional"))
    )
    (net (code "45") (name "Net-(Q2-G)") (class "Default")
      (node (ref "IC5") (pin "17") (pinfunction "17_17") (pintype "passive"))
      (node (ref "Q2") (pin "1") (pinfunction "G_1") (pintype "bidirectional"))
      (node (ref "R2") (pin "1") (pinfunction "1_1") (pintype "passive"))
    )
    (net (code "46") (name "Net-(Q3-D)") (class "Default")
      (node (ref "C3") (pin "1") (pinfunction "1_1") (pintype "passive"))
      (node (ref "D3") (pin "A") (pinfunction "A_A") (pintype "passive"))
      (node (ref "J4") (pin "1") (pinfunction "1_1") (pintype "passive"))
      (node (ref "Q3") (pin "2") (pinfunction "D_2") (pintype "bidirectional"))
    )
    (net (code "47") (name "Net-(Q3-G)") (class "Default")
      (node (ref "IC5") (pin "16") (pinfunction "16_16") (pintype "passive"))
      (node (ref "Q3") (pin "1") (pinfunction "G_1") (pintype "bidirectional"))
      (node (ref "R3") (pin "1") (pinfunction "1_1") (pintype "passive"))
    )
    (net (code "48") (name "Net-(Q4-D)") (class "Default")
      (node (ref "C4") (pin "1") (pinfunction "1_1") (pintype "passive"))
      (node (ref "D4") (pin "A") (pinfunction "A_A") (pintype "passive"))
      (node (ref "J5") (pin "1") (pinfunction "1_1") (pintype "passive"))
      (node (ref "Q4") (pin "2") (pinfunction "D_2") (pintype "bidirectional"))
    )
    (net (code "49") (name "Net-(Q4-G)") (class "Default")
      (node (ref "IC5") (pin "15") (pinfunction "15_15") (pintype "passive"))
      (node (ref "Q4") (pin "1") (pinfunction "G_1") (pintype "bidirectional"))
      (node (ref "R4") (pin "1") (pinfunction "1_1") (pintype "passive"))
    )
    (net (code "50") (name "Net-(Q5-D)") (class "Default")
      (node (ref "C5") (pin "1") (pinfunction "1_1") (pintype "passive"))
      (node (ref "D5") (pin "A") (pinfunction "A_A") (pintype "passive"))
      (node (ref "J6") (pin "1") (pinfunction "1_1") (pintype "passive"))
      (node (ref "Q5") (pin "2") (pinfunction "D_2") (pintype "bidirectional"))
    )
    (net (code "51") (name "Net-(Q5-G)") (class "Default")
      (node (ref "IC5") (pin "14") (pinfunction "14_14") (pintype "passive"))
      (node (ref "Q5") (pin "1") (pinfunction "G_1") (pintype "bidirectional"))
      (node (ref "R5") (pin "2") (pinfunction "2_2") (pintype "passive"))
    )
    (net (code "52") (name "Net-(Q6-D)") (class "Default")
      (node (ref "C6") (pin "1") (pinfunction "1_1") (pintype "passive"))
      (node (ref "D6") (pin "A") (pinfunction "A_A") (pintype "passive"))
      (node (ref "J7") (pin "1") (pinfunction "1_1") (pintype "passive"))
      (node (ref "Q6") (pin "2") (pinfunction "D_2") (pintype "bidirectional"))
    )
    (net (code "53") (name "Net-(Q6-G)") (class "Default")
      (node (ref "IC5") (pin "13") (pinfunction "13_13") (pintype "passive"))
      (node (ref "Q6") (pin "1") (pinfunction "G_1") (pintype "bidirectional"))
      (node (ref "R6") (pin "2") (pinfunction "2_2") (pintype "passive"))
    )
    (net (code "54") (name "Net-(Q7-D)") (class "Default")
      (node (ref "C7") (pin "1") (pinfunction "1_1") (pintype "passive"))
      (node (ref "D7") (pin "A") (pinfunction "A_A") (pintype "passive"))
      (node (ref "J8") (pin "1") (pinfunction "1_1") (pintype "passive"))
      (node (ref "Q7") (pin "2") (pinfunction "D_2") (pintype "bidirectional"))
    )
    (net (code "55") (name "Net-(Q7-G)") (class "Default")
      (node (ref "IC5") (pin "12") (pinfunction "12_12") (pintype "passive"))
      (node (ref "Q7") (pin "1") (pinfunction "G_1") (pintype "bidirectional"))
      (node (ref "R7") (pin "2") (pinfunction "2_2") (pintype "passive"))
    )
    (net (code "56") (name "Net-(Q8-D)") (class "Default")
      (node (ref "C8") (pin "1") (pinfunction "1_1") (pintype "passive"))
      (node (ref "D8") (pin "A") (pinfunction "A_A") (pintype "passive"))
      (node (ref "J16") (pin "1") (pinfunction "1_1") (pintype "passive"))
      (node (ref "Q8") (pin "2") (pinfunction "D_2") (pintype "bidirectional"))
    )
    (net (code "57") (name "Net-(Q8-G)") (class "Default")
      (node (ref "IC5") (pin "11") (pinfunction "11_11") (pintype "passive"))
      (node (ref "Q8") (pin "1") (pinfunction "G_1") (pintype "bidirectional"))
      (node (ref "R8") (pin "1") (pinfunction "1_1") (pintype "passive"))
    )
    (net (code "58") (name "Net-(Q9-D)") (class "Default")
      (node (ref "C9") (pin "1") (pinfunction "1_1") (pintype "passive"))
      (node (ref "D9") (pin "A") (pinfunction "A_A") (pintype "passive"))
      (node (ref "J17") (pin "1") (pinfunction "1_1") (pintype "passive"))
      (node (ref "Q9") (pin "2") (pinfunction "D_2") (pintype "bidirectional"))
    )
    (net (code "59") (name "Net-(Q9-G)") (class "Default")
      (node (ref "IC6") (pin "18") (pinfunction "18_18") (pintype "passive"))
      (node (ref "Q9") (pin "1") (pinfunction "G_1") (pintype "bidirectional"))
      (node (ref "R9") (pin "1") (pinfunction "1_1") (pintype "passive"))
    )
    (net (code "60") (name "Net-(Q10-D)") (class "Default")
      (node (ref "C10") (pin "1") (pinfunction "1_1") (pintype "passive"))
      (node (ref "D10") (pin "A") (pinfunction "A_A") (pintype "passive"))
      (node (ref "J18") (pin "1") (pinfunction "1_1") (pintype "passive"))
      (node (ref "Q10") (pin "2") (pinfunction "D_2") (pintype "bidirectional"))
    )
    (net (code "61") (name "Net-(Q10-G)") (class "Default")
      (node (ref "IC6") (pin "17") (pinfunction "17_17") (pintype "passive"))
      (node (ref "Q10") (pin "1") (pinfunction "G_1") (pintype "bidirectional"))
      (node (ref "R10") (pin "1") (pinfunction "1_1") (pintype "passive"))
    )
    (net (code "62") (name "Net-(Q11-D)") (class "Default")
      (node (ref "C11") (pin "1") (pinfunction "1_1") (pintype "passive"))
      (node (ref "D11") (pin "A") (pinfunction "A_A") (pintype "passive"))
      (node (ref "J19") (pin "1") (pinfunction "1_1") (pintype "passive"))
      (node (ref "Q11") (pin "2") (pinfunction "D_2") (pintype "bidirectional"))
    )
    (net (code "63") (name "Net-(Q11-G)") (class "Default")
      (node (ref "IC6") (pin "16") (pinfunction "16_16") (pintype "passive"))
      (node (ref "Q11") (pin "1") (pinfunction "G_1") (pintype "bidirectional"))
      (node (ref "R11") (pin "1") (pinfunction "1_1") (pintype "passive"))
    )
    (net (code "64") (name "Net-(Q12-D)") (class "Default")
      (node (ref "C12") (pin "1") (pinfunction "1_1") (pintype "passive"))
      (node (ref "D12") (pin "A") (pinfunction "A_A") (pintype "passive"))
      (node (ref "J20") (pin "1") (pinfunction "1_1") (pintype "passive"))
      (node (ref "Q12") (pin "2") (pinfunction "D_2") (pintype "bidirectional"))
    )
    (net (code "65") (name "Net-(Q12-G)") (class "Default")
      (node (ref "IC6") (pin "15") (pinfunction "15_15") (pintype "passive"))
      (node (ref "Q12") (pin "1") (pinfunction "G_1") (pintype "bidirectional"))
      (node (ref "R12") (pin "2") (pinfunction "2_2") (pintype "passive"))
    )
    (net (code "66") (name "Net-(Q13-D)") (class "Default")
      (node (ref "C13") (pin "1") (pinfunction "1_1") (pintype "passive"))
      (node (ref "D13") (pin "A") (pinfunction "A_A") (pintype "passive"))
      (node (ref "J21") (pin "1") (pinfunction "1_1") (pintype "passive"))
      (node (ref "Q13") (pin "2") (pinfunction "D_2") (pintype "bidirectional"))
    )
    (net (code "67") (name "Net-(Q13-G)") (class "Default")
      (node (ref "IC6") (pin "14") (pinfunction "14_14") (pintype "passive"))
      (node (ref "Q13") (pin "1") (pinfunction "G_1") (pintype "bidirectional"))
      (node (ref "R13") (pin "2") (pinfunction "2_2") (pintype "passive"))
    )
    (net (code "68") (name "VCC") (class "Default")
      (node (ref "U1") (pin "8") (pinfunction "VCC_8") (pintype "bidirectional"))
      (node (ref "U10") (pin "8") (pinfunction "VCC_8") (pintype "bidirectional"))
      (node (ref "U11") (pin "8") (pinfunction "VCC_8") (pintype "bidirectional"))
      (node (ref "U12") (pin "8") (pinfunction "VCC_8") (pintype "bidirectional"))
      (node (ref "U13") (pin "8") (pinfunction "VCC_8") (pintype "bidirectional"))
      (node (ref "U2") (pin "8") (pinfunction "VCC_8") (pintype "bidirectional"))
      (node (ref "U3") (pin "8") (pinfunction "VCC_8") (pintype "bidirectional"))
      (node (ref "U4") (pin "8") (pinfunction "VCC_8") (pintype "bidirectional"))
      (node (ref "U5") (pin "8") (pinfunction "VCC_8") (pintype "bidirectional"))
      (node (ref "U6") (pin "8") (pinfunction "VCC_8") (pintype "bidirectional"))
      (node (ref "U7") (pin "8") (pinfunction "VCC_8") (pintype "bidirectional"))
      (node (ref "U8") (pin "8") (pinfunction "VCC_8") (pintype "bidirectional"))
      (node (ref "U9") (pin "8") (pinfunction "VCC_8") (pintype "bidirectional"))
      (node (ref "VCC") (pin "1") (pinfunction "1_1") (pintype "passive"))
    )
    (net (code "69") (name "unconnected-(IC6-Pad6)") (class "Default")
      (node (ref "IC6") (pin "6") (pinfunction "6_6") (pintype "passive"))
    )
    (net (code "70") (name "unconnected-(IC6-Pad7)") (class "Default")
      (node (ref "IC6") (pin "7") (pinfunction "7_7") (pintype "passive"))
    )
    (net (code "71") (name "unconnected-(IC6-Pad8)") (class "Default")
      (node (ref "IC6") (pin "8") (pinfunction "8_8") (pintype "passive"))
    )
    (net (code "72") (name "unconnected-(IC6-Pad11)") (class "Default")
      (node (ref "IC6") (pin "11") (pinfunction "11_11") (pintype "passive"))
    )
    (net (code "73") (name "unconnected-(IC6-Pad12)") (class "Default")
      (node (ref "IC6") (pin "12") (pinfunction "12_12") (pintype "passive"))
    )
    (net (code "74") (name "unconnected-(IC6-Pad13)") (class "Default")
      (node (ref "IC6") (pin "13") (pinfunction "13_13") (pintype "passive"))
    )
    (net (code "75") (name "unconnected-(U1-PB0(MOSI)-Pad5)") (class "Default")
      (node (ref "U1") (pin "5") (pinfunction "PB0(MOSI)_5") (pintype "bidirectional"))
    )
    (net (code "76") (name "unconnected-(U1-PB1(MISO)-Pad6)") (class "Default")
      (node (ref "U1") (pin "6") (pinfunction "PB1(MISO)_6") (pintype "bidirectional"))
    )
    (net (code "77") (name "unconnected-(U1-PB2(SCK{slash}ADC1)-Pad7)") (class "Default")
      (node (ref "U1") (pin "7") (pinfunction "PB2(SCK/ADC1)_7") (pintype "bidirectional"))
    )
    (net (code "78") (name "unconnected-(U1-PB3(ADC3)-Pad2)") (class "Default")
      (node (ref "U1") (pin "2") (pinfunction "PB3(ADC3)_2") (pintype "bidirectional"))
    )
    (net (code "79") (name "unconnected-(U1-PB5(NRES)-Pad1)") (class "Default")
      (node (ref "U1") (pin "1") (pinfunction "PB5(NRES)_1") (pintype "bidirectional"))
    )
    (net (code "80") (name "unconnected-(U2-PB0(MOSI)-Pad5)") (class "Default")
      (node (ref "U2") (pin "5") (pinfunction "PB0(MOSI)_5") (pintype "bidirectional"))
    )
    (net (code "81") (name "unconnected-(U2-PB1(MISO)-Pad6)") (class "Default")
      (node (ref "U2") (pin "6") (pinfunction "PB1(MISO)_6") (pintype "bidirectional"))
    )
    (net (code "82") (name "unconnected-(U2-PB2(SCK{slash}ADC1)-Pad7)") (class "Default")
      (node (ref "U2") (pin "7") (pinfunction "PB2(SCK/ADC1)_7") (pintype "bidirectional"))
    )
    (net (code "83") (name "unconnected-(U2-PB3(ADC3)-Pad2)") (class "Default")
      (node (ref "U2") (pin "2") (pinfunction "PB3(ADC3)_2") (pintype "bidirectional"))
    )
    (net (code "84") (name "unconnected-(U2-PB5(NRES)-Pad1)") (class "Default")
      (node (ref "U2") (pin "1") (pinfunction "PB5(NRES)_1") (pintype "bidirectional"))
    )
    (net (code "85") (name "unconnected-(U3-PB0(MOSI)-Pad5)") (class "Default")
      (node (ref "U3") (pin "5") (pinfunction "PB0(MOSI)_5") (pintype "bidirectional"))
    )
    (net (code "86") (name "unconnected-(U3-PB1(MISO)-Pad6)") (class "Default")
      (node (ref "U3") (pin "6") (pinfunction "PB1(MISO)_6") (pintype "bidirectional"))
    )
    (net (code "87") (name "unconnected-(U3-PB2(SCK{slash}ADC1)-Pad7)") (class "Default")
      (node (ref "U3") (pin "7") (pinfunction "PB2(SCK/ADC1)_7") (pintype "bidirectional"))
    )
    (net (code "88") (name "unconnected-(U3-PB3(ADC3)-Pad2)") (class "Default")
      (node (ref "U3") (pin "2") (pinfunction "PB3(ADC3)_2") (pintype "bidirectional"))
    )
    (net (code "89") (name "unconnected-(U3-PB5(NRES)-Pad1)") (class "Default")
      (node (ref "U3") (pin "1") (pinfunction "PB5(NRES)_1") (pintype "bidirectional"))
    )
    (net (code "90") (name "unconnected-(U4-PB0(MOSI)-Pad5)") (class "Default")
      (node (ref "U4") (pin "5") (pinfunction "PB0(MOSI)_5") (pintype "bidirectional"))
    )
    (net (code "91") (name "unconnected-(U4-PB1(MISO)-Pad6)") (class "Default")
      (node (ref "U4") (pin "6") (pinfunction "PB1(MISO)_6") (pintype "bidirectional"))
    )
    (net (code "92") (name "unconnected-(U4-PB2(SCK{slash}ADC1)-Pad7)") (class "Default")
      (node (ref "U4") (pin "7") (pinfunction "PB2(SCK/ADC1)_7") (pintype "bidirectional"))
    )
    (net (code "93") (name "unconnected-(U4-PB3(ADC3)-Pad2)") (class "Default")
      (node (ref "U4") (pin "2") (pinfunction "PB3(ADC3)_2") (pintype "bidirectional"))
    )
    (net (code "94") (name "unconnected-(U4-PB5(NRES)-Pad1)") (class "Default")
      (node (ref "U4") (pin "1") (pinfunction "PB5(NRES)_1") (pintype "bidirectional"))
    )
    (net (code "95") (name "unconnected-(U5-PB0(MOSI)-Pad5)") (class "Default")
      (node (ref "U5") (pin "5") (pinfunction "PB0(MOSI)_5") (pintype "bidirectional"))
    )
    (net (code "96") (name "unconnected-(U5-PB1(MISO)-Pad6)") (class "Default")
      (node (ref "U5") (pin "6") (pinfunction "PB1(MISO)_6") (pintype "bidirectional"))
    )
    (net (code "97") (name "unconnected-(U5-PB2(SCK{slash}ADC1)-Pad7)") (class "Default")
      (node (ref "U5") (pin "7") (pinfunction "PB2(SCK/ADC1)_7") (pintype "bidirectional"))
    )
    (net (code "98") (name "unconnected-(U5-PB3(ADC3)-Pad2)") (class "Default")
      (node (ref "U5") (pin "2") (pinfunction "PB3(ADC3)_2") (pintype "bidirectional"))
    )
    (net (code "99") (name "unconnected-(U5-PB5(NRES)-Pad1)") (class "Default")
      (node (ref "U5") (pin "1") (pinfunction "PB5(NRES)_1") (pintype "bidirectional"))
    )
    (net (code "100") (name "unconnected-(U6-PB0(MOSI)-Pad5)") (class "Default")
      (node (ref "U6") (pin "5") (pinfunction "PB0(MOSI)_5") (pintype "bidirectional"))
    )
    (net (code "101") (name "unconnected-(U6-PB1(MISO)-Pad6)") (class "Default")
      (node (ref "U6") (pin "6") (pinfunction "PB1(MISO)_6") (pintype "bidirectional"))
    )
    (net (code "102") (name "unconnected-(U6-PB2(SCK{slash}ADC1)-Pad7)") (class "Default")
      (node (ref "U6") (pin "7") (pinfunction "PB2(SCK/ADC1)_7") (pintype "bidirectional"))
    )
    (net (code "103") (name "unconnected-(U6-PB3(ADC3)-Pad2)") (class "Default")
      (node (ref "U6") (pin "2") (pinfunction "PB3(ADC3)_2") (pintype "bidirectional"))
    )
    (net (code "104") (name "unconnected-(U6-PB5(NRES)-Pad1)") (class "Default")
      (node (ref "U6") (pin "1") (pinfunction "PB5(NRES)_1") (pintype "bidirectional"))
    )
    (net (code "105") (name "unconnected-(U7-PB0(MOSI)-Pad5)") (class "Default")
      (node (ref "U7") (pin "5") (pinfunction "PB0(MOSI)_5") (pintype "bidirectional"))
    )
    (net (code "106") (name "unconnected-(U7-PB1(MISO)-Pad6)") (class "Default")
      (node (ref "U7") (pin "6") (pinfunction "PB1(MISO)_6") (pintype "bidirectional"))
    )
    (net (code "107") (name "unconnected-(U7-PB2(SCK{slash}ADC1)-Pad7)") (class "Default")
      (node (ref "U7") (pin "7") (pinfunction "PB2(SCK/ADC1)_7") (pintype "bidirectional"))
    )
    (net (code "108") (name "unconnected-(U7-PB3(ADC3)-Pad2)") (class "Default")
      (node (ref "U7") (pin "2") (pinfunction "PB3(ADC3)_2") (pintype "bidirectional"))
    )
    (net (code "109") (name "unconnected-(U7-PB5(NRES)-Pad1)") (class "Default")
      (node (ref "U7") (pin "1") (pinfunction "PB5(NRES)_1") (pintype "bidirectional"))
    )
    (net (code "110") (name "unconnected-(U8-PB0(MOSI)-Pad5)") (class "Default")
      (node (ref "U8") (pin "5") (pinfunction "PB0(MOSI)_5") (pintype "bidirectional"))
    )
    (net (code "111") (name "unconnected-(U8-PB1(MISO)-Pad6)") (class "Default")
      (node (ref "U8") (pin "6") (pinfunction "PB1(MISO)_6") (pintype "bidirectional"))
    )
    (net (code "112") (name "unconnected-(U8-PB2(SCK{slash}ADC1)-Pad7)") (class "Default")
      (node (ref "U8") (pin "7") (pinfunction "PB2(SCK/ADC1)_7") (pintype "bidirectional"))
    )
    (net (code "113") (name "unconnected-(U8-PB3(ADC3)-Pad2)") (class "Default")
      (node (ref "U8") (pin "2") (pinfunction "PB3(ADC3)_2") (pintype "bidirectional"))
    )
    (net (code "114") (name "unconnected-(U8-PB5(NRES)-Pad1)") (class "Default")
      (node (ref "U8") (pin "1") (pinfunction "PB5(NRES)_1") (pintype "bidirectional"))
    )
    (net (code "115") (name "unconnected-(U9-PB0(MOSI)-Pad5)") (class "Default")
      (node (ref "U9") (pin "5") (pinfunction "PB0(MOSI)_5") (pintype "bidirectional"))
    )
    (net (code "116") (name "unconnected-(U9-PB1(MISO)-Pad6)") (class "Default")
      (node (ref "U9") (pin "6") (pinfunction "PB1(MISO)_6") (pintype "bidirectional"))
    )
    (net (code "117") (name "unconnected-(U9-PB2(SCK{slash}ADC1)-Pad7)") (class "Default")
      (node (ref "U9") (pin "7") (pinfunction "PB2(SCK/ADC1)_7") (pintype "bidirectional"))
    )
    (net (code "118") (name "unconnected-(U9-PB3(ADC3)-Pad2)") (class "Default")
      (node (ref "U9") (pin "2") (pinfunction "PB3(ADC3)_2") (pintype "bidirectional"))
    )
    (net (code "119") (name "unconnected-(U9-PB5(NRES)-Pad1)") (class "Default")
      (node (ref "U9") (pin "1") (pinfunction "PB5(NRES)_1") (pintype "bidirectional"))
    )
    (net (code "120") (name "unconnected-(U10-PB0(MOSI)-Pad5)") (class "Default")
      (node (ref "U10") (pin "5") (pinfunction "PB0(MOSI)_5") (pintype "bidirectional"))
    )
    (net (code "121") (name "unconnected-(U10-PB1(MISO)-Pad6)") (class "Default")
      (node (ref "U10") (pin "6") (pinfunction "PB1(MISO)_6") (pintype "bidirectional"))
    )
    (net (code "122") (name "unconnected-(U10-PB2(SCK{slash}ADC1)-Pad7)") (class "Default")
      (node (ref "U10") (pin "7") (pinfunction "PB2(SCK/ADC1)_7") (pintype "bidirectional"))
    )
    (net (code "123") (name "unconnected-(U10-PB3(ADC3)-Pad2)") (class "Default")
      (node (ref "U10") (pin "2") (pinfunction "PB3(ADC3)_2") (pintype "bidirectional"))
    )
    (net (code "124") (name "unconnected-(U10-PB5(NRES)-Pad1)") (class "Default")
      (node (ref "U10") (pin "1") (pinfunction "PB5(NRES)_1") (pintype "bidirectional"))
    )
    (net (code "125") (name "unconnected-(U11-PB0(MOSI)-Pad5)") (class "Default")
      (node (ref "U11") (pin "5") (pinfunction "PB0(MOSI)_5") (pintype "bidirectional"))
    )
    (net (code "126") (name "unconnected-(U11-PB1(MISO)-Pad6)") (class "Default")
      (node (ref "U11") (pin "6") (pinfunction "PB1(MISO)_6") (pintype "bidirectional"))
    )
    (net (code "127") (name "unconnected-(U11-PB2(SCK{slash}ADC1)-Pad7)") (class "Default")
      (node (ref "U11") (pin "7") (pinfunction "PB2(SCK/ADC1)_7") (pintype "bidirectional"))
    )
    (net (code "128") (name "unconnected-(U11-PB3(ADC3)-Pad2)") (class "Default")
      (node (ref "U11") (pin "2") (pinfunction "PB3(ADC3)_2") (pintype "bidirectional"))
    )
    (net (code "129") (name "unconnected-(U11-PB5(NRES)-Pad1)") (class "Default")
      (node (ref "U11") (pin "1") (pinfunction "PB5(NRES)_1") (pintype "bidirectional"))
    )
    (net (code "130") (name "unconnected-(U12-PB0(MOSI)-Pad5)") (class "Default")
      (node (ref "U12") (pin "5") (pinfunction "PB0(MOSI)_5") (pintype "bidirectional"))
    )
    (net (code "131") (name "unconnected-(U12-PB1(MISO)-Pad6)") (class "Default")
      (node (ref "U12") (pin "6") (pinfunction "PB1(MISO)_6") (pintype "bidirectional"))
    )
    (net (code "132") (name "unconnected-(U12-PB2(SCK{slash}ADC1)-Pad7)") (class "Default")
      (node (ref "U12") (pin "7") (pinfunction "PB2(SCK/ADC1)_7") (pintype "bidirectional"))
    )
    (net (code "133") (name "unconnected-(U12-PB3(ADC3)-Pad2)") (class "Default")
      (node (ref "U12") (pin "2") (pinfunction "PB3(ADC3)_2") (pintype "bidirectional"))
    )
    (net (code "134") (name "unconnected-(U12-PB5(NRES)-Pad1)") (class "Default")
      (node (ref "U12") (pin "1") (pinfunction "PB5(NRES)_1") (pintype "bidirectional"))
    )
    (net (code "135") (name "unconnected-(U13-PB0(MOSI)-Pad5)") (class "Default")
      (node (ref "U13") (pin "5") (pinfunction "PB0(MOSI)_5") (pintype "bidirectional"))
    )
    (net (code "136") (name "unconnected-(U13-PB1(MISO)-Pad6)") (class "Default")
      (node (ref "U13") (pin "6") (pinfunction "PB1(MISO)_6") (pintype "bidirectional"))
    )
    (net (code "137") (name "unconnected-(U13-PB2(SCK{slash}ADC1)-Pad7)") (class "Default")
      (node (ref "U13") (pin "7") (pinfunction "PB2(SCK/ADC1)_7") (pintype "bidirectional"))
    )
    (net (code "138") (name "unconnected-(U13-PB3(ADC3)-Pad2)") (class "Default")
      (node (ref "U13") (pin "2") (pinfunction "PB3(ADC3)_2") (pintype "bidirectional"))
    )
    (net (code "139") (name "unconnected-(U13-PB5(NRES)-Pad1)") (class "Default")
      (node (ref "U13") (pin "1") (pinfunction "PB5(NRES)_1") (pintype "bidirectional"))
    )
  )
)
